# MAIN.net
KiCad netlist of a schematic drawn in Altium Designer
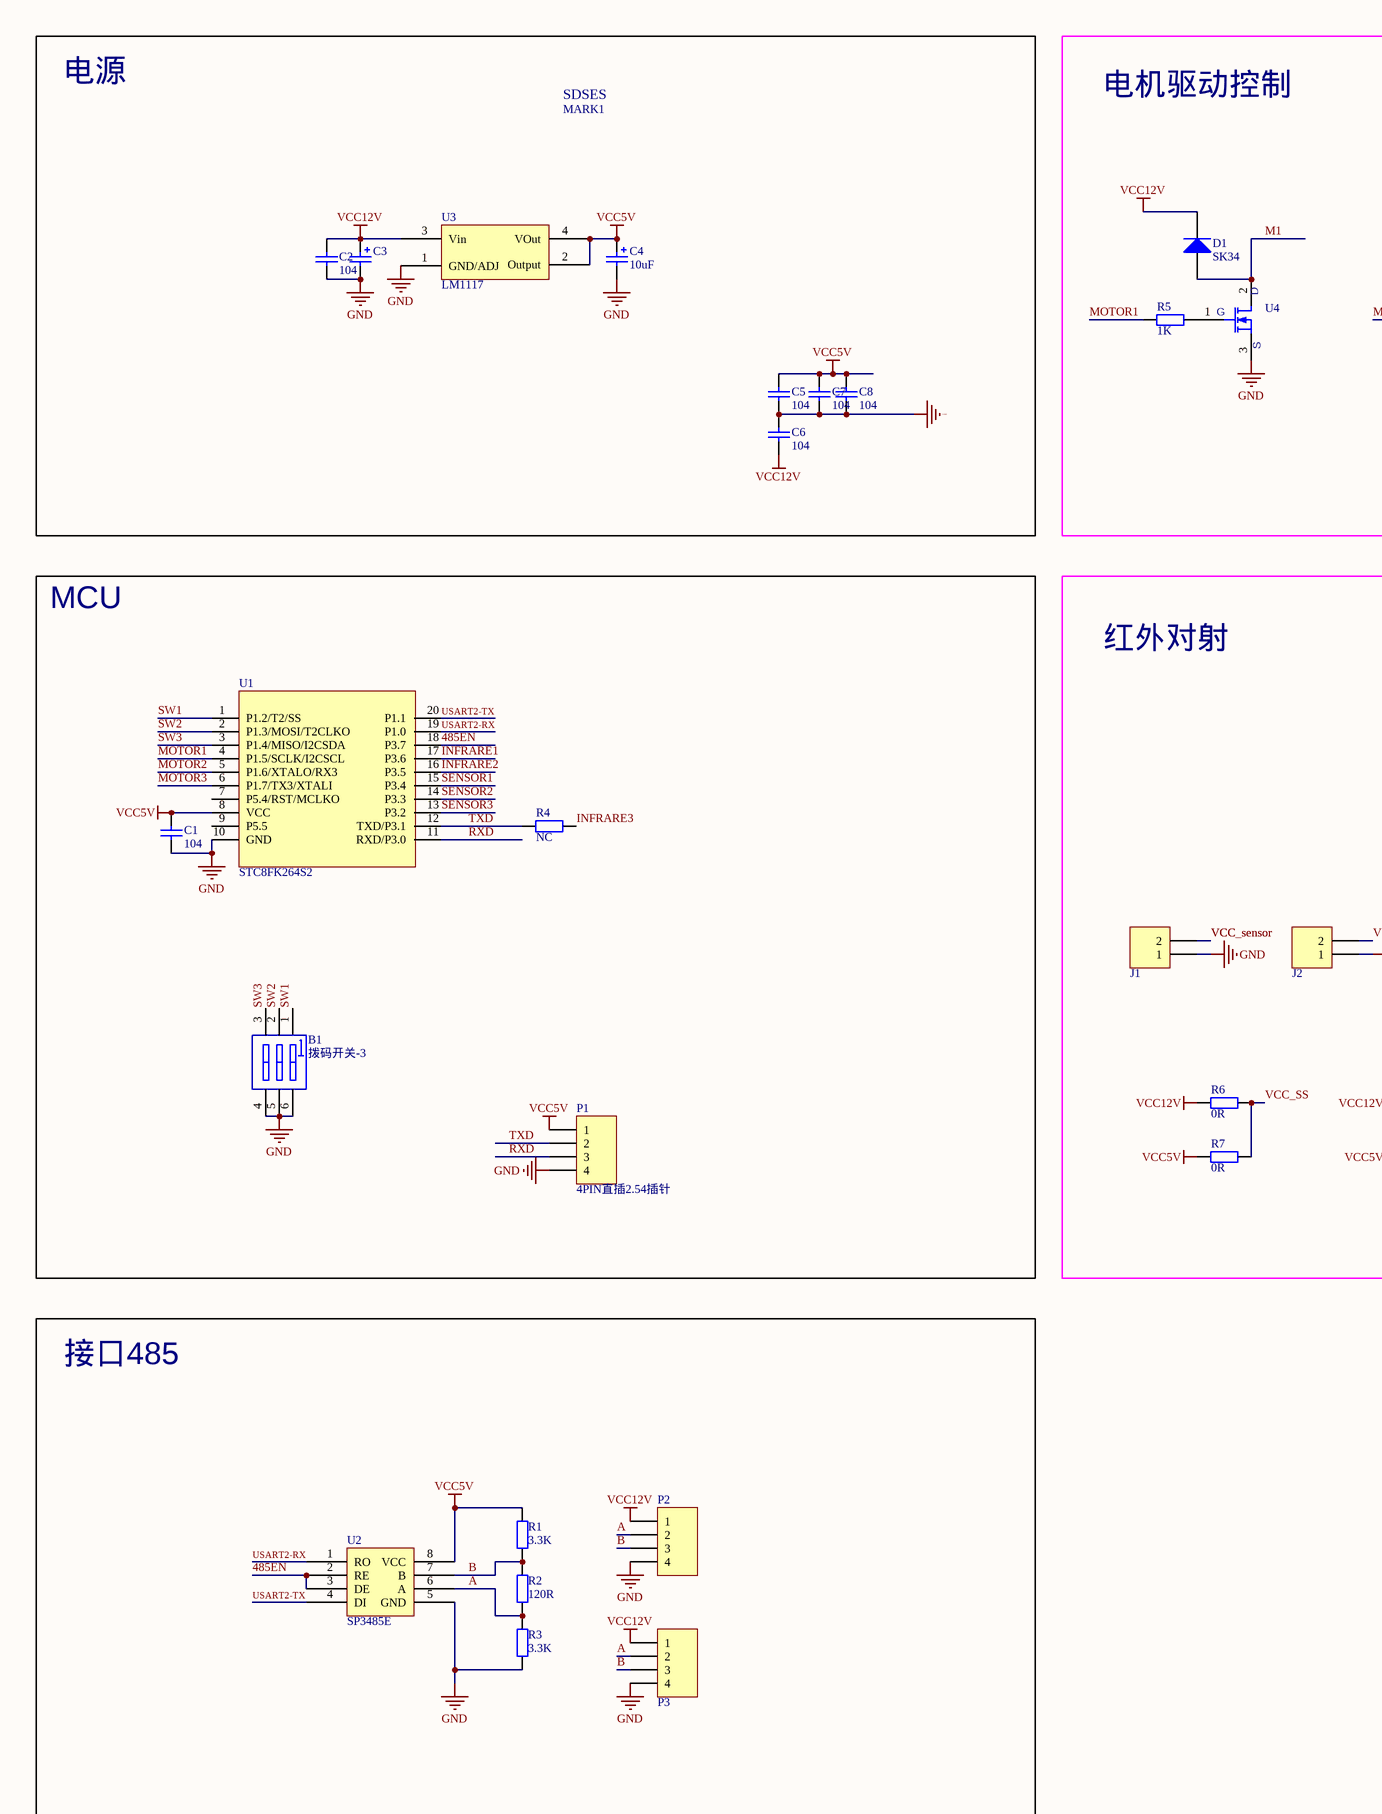
[diagram p0: MAIN.SchDoc, left]
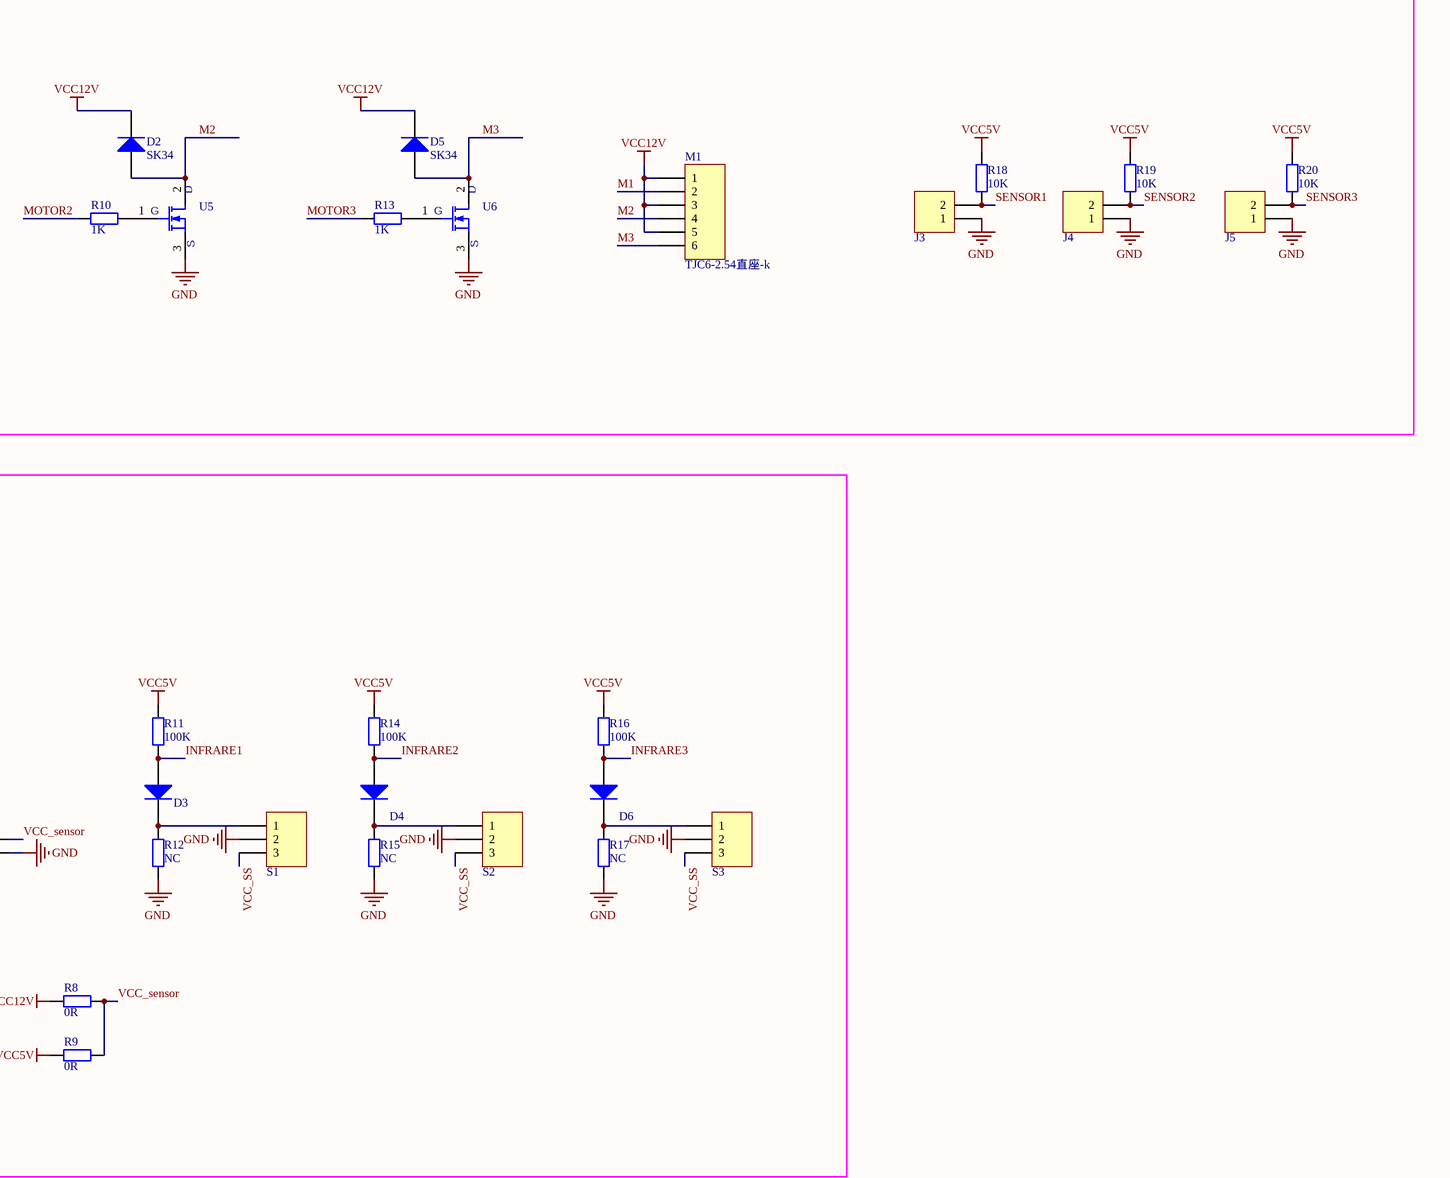
[diagram p1: MAIN.SchDoc, right]

(export (version "E")
  (design (tool "Eeschema 10.0.6"))
  (components
    (comp (ref "B1") (value "拨码开关-3") (footprint "DS-03-2.54") (libsource (lib "接插件") (part "拨码开关-3")))
    (comp (ref "C1")
      (value "Cap_0603")
      (footprint "0603C")
      (fields (field (name "型号") "104"))
      (libsource (lib "阻容晶体管元件") (part "Cap_0603"))
    )
    (comp (ref "C2")
      (value "Cap_0603")
      (footprint "0603C")
      (fields (field (name "型号") "104"))
      (libsource (lib "阻容晶体管元件") (part "Cap_0603"))
    )
    (comp (ref "C3")
      (value "Cap_直插470uf/16v")
      (footprint "cap_470/16v")
      (description "Polarized Capacitor (Radial)")
      (libsource (lib "阻容晶体管元件") (part "Cap_直插470uf/16v"))
    )
    (comp (ref "C4")
      (value "Cap_钽电容B-3528")
      (footprint "0805C")
      (description "Polarized Capacitor (Radial)")
      (fields (field (name "型号") "10uF"))
      (libsource (lib "阻容晶体管元件") (part "Cap_钽电容B-3528"))
    )
    (comp (ref "C5")
      (value "Cap_0603")
      (footprint "0603C")
      (fields (field (name "型号") "104"))
      (libsource (lib "阻容晶体管元件") (part "Cap_0603"))
    )
    (comp (ref "C6")
      (value "Cap_0603")
      (footprint "0603C")
      (fields (field (name "型号") "104"))
      (libsource (lib "阻容晶体管元件") (part "Cap_0603"))
    )
    (comp (ref "C7")
      (value "Cap_0603")
      (footprint "0603C")
      (fields (field (name "型号") "104"))
      (libsource (lib "阻容晶体管元件") (part "Cap_0603"))
    )
    (comp (ref "C8")
      (value "Cap_0603")
      (footprint "0603C")
      (fields (field (name "型号") "104"))
      (libsource (lib "阻容晶体管元件") (part "Cap_0603"))
    )
    (comp (ref "D1")
      (value "Diode_DO214AC")
      (footprint "DO_214AC_SMA")
      (description "Default Diode")
      (fields (field (name "型号") "SK34"))
      (libsource (lib "阻容晶体管元件") (part "Diode_DO214AC"))
    )
    (comp (ref "D2")
      (value "Diode_DO214AC")
      (footprint "DO_214AC_SMA")
      (description "Default Diode")
      (fields (field (name "型号") "SK34"))
      (libsource (lib "阻容晶体管元件") (part "Diode_DO214AC"))
    )
    (comp (ref "D3")
      (value "Diode_SOD323")
      (footprint "SOD323_D")
      (description "Default Diode")
      (fields (field (name "PUBLISHER") "Altium Limited"))
      (libsource (lib "阻容晶体管元件") (part "Diode_SOD323"))
    )
    (comp (ref "D4")
      (value "Diode_SOD323")
      (footprint "SOD323_D")
      (description "Default Diode")
      (fields (field (name "PUBLISHER") "Altium Limited"))
      (libsource (lib "阻容晶体管元件") (part "Diode_SOD323"))
    )
    (comp (ref "D5")
      (value "Diode_DO214AC")
      (footprint "DO_214AC_SMA")
      (description "Default Diode")
      (fields (field (name "型号") "SK34"))
      (libsource (lib "阻容晶体管元件") (part "Diode_DO214AC"))
    )
    (comp (ref "D6")
      (value "Diode_SOD323")
      (footprint "SOD323_D")
      (description "Default Diode")
      (fields (field (name "PUBLISHER") "Altium Limited"))
      (libsource (lib "阻容晶体管元件") (part "Diode_SOD323"))
    )
    (comp (ref "J1")
      (value "XHB2.54-2PIN-带锁扣")
      (footprint "SIP2")
      (description "Header, 4-Pin")
      (libsource (lib "接插件") (part "XHB2.54-2P直座"))
    )
    (comp (ref "J2")
      (value "XHB2.54-2PIN-带锁扣")
      (footprint "SIP2")
      (description "Header, 4-Pin")
      (libsource (lib "接插件") (part "XHB2.54-2P直座"))
    )
    (comp (ref "J3")
      (value "XHB2.54-2PIN-带锁扣")
      (footprint "SIP2")
      (description "Header, 4-Pin")
      (libsource (lib "接插件") (part "XHB2.54-2P直座"))
    )
    (comp (ref "J4")
      (value "XHB2.54-2PIN-带锁扣")
      (footprint "SIP2")
      (description "Header, 4-Pin")
      (libsource (lib "接插件") (part "XHB2.54-2P直座"))
    )
    (comp (ref "J5")
      (value "XHB2.54-2PIN-带锁扣")
      (footprint "SIP2")
      (description "Header, 4-Pin")
      (libsource (lib "接插件") (part "XHB2.54-2P直座"))
    )
    (comp (ref "M1")
      (value "TJC6-2.54直座-k")
      (footprint "SIP6")
      (description "Header, 6-Pin")
      (libsource (lib "接插件") (part "TJC6-2.54直座-k"))
    )
    (comp (ref "MARK1") (value "SDSES") (footprint "SDSES") (libsource (lib "集成电路") (part "SDSES")))
    (comp (ref "P1")
      (value "4PIN直插2.54插针")
      (footprint "SIP4_2D54F")
      (description "Header, 4-Pin")
      (libsource (lib "接插件") (part "4PIN直插2.54插针"))
    )
    (comp (ref "P2")
      (value "XHB2.54-4PIN直座")
      (footprint "SIP4")
      (description "Header, 4-Pin")
      (libsource (lib "接插件") (part "XHB2.54-4PIN直座"))
    )
    (comp (ref "P3")
      (value "XHB2.54-4PIN直座")
      (footprint "SIP4")
      (description "Header, 4-Pin")
      (libsource (lib "接插件") (part "XHB2.54-4PIN直座"))
    )
    (comp (ref "R1")
      (value "Res_0603")
      (footprint "0603R")
      (description "Resistor")
      (fields (field (name "型号") "3.3K"))
      (libsource (lib "") (part "Res_0603_1"))
    )
    (comp (ref "R2")
      (value "Res_0603")
      (footprint "0603R")
      (description "Resistor")
      (fields (field (name "型号") "120R"))
      (libsource (lib "") (part "Res_0603_1"))
    )
    (comp (ref "R3")
      (value "Res_0603")
      (footprint "0603R")
      (description "Resistor")
      (fields (field (name "型号") "3.3K"))
      (libsource (lib "") (part "Res_0603_1"))
    )
    (comp (ref "R4")
      (value "Res_0603")
      (footprint "0603R")
      (description "Resistor")
      (fields (field (name "型号") "NC"))
      (libsource (lib "") (part "Res_0603_3"))
    )
    (comp (ref "R5")
      (value "Res_0603")
      (footprint "0603R")
      (description "Resistor")
      (fields (field (name "型号") "1K"))
      (libsource (lib "阻容晶体管元件") (part "Res_0603"))
    )
    (comp (ref "R6")
      (value "Res_0603")
      (footprint "0603R")
      (description "Resistor")
      (fields (field (name "型号") "0R"))
      (libsource (lib "") (part "Res_0603_3"))
    )
    (comp (ref "R7")
      (value "Res_0603")
      (footprint "0603R")
      (description "Resistor")
      (fields (field (name "型号") "0R"))
      (libsource (lib "") (part "Res_0603_3"))
    )
    (comp (ref "R8")
      (value "Res_0603")
      (footprint "0603R")
      (description "Resistor")
      (fields (field (name "型号") "0R"))
      (libsource (lib "") (part "Res_0603_3"))
    )
    (comp (ref "R9")
      (value "Res_0603")
      (footprint "0603R")
      (description "Resistor")
      (fields (field (name "型号") "0R"))
      (libsource (lib "") (part "Res_0603_3"))
    )
    (comp (ref "R10")
      (value "Res_0603")
      (footprint "0603R")
      (description "Resistor")
      (fields (field (name "型号") "1K"))
      (libsource (lib "阻容晶体管元件") (part "Res_0603"))
    )
    (comp (ref "R11")
      (value "Res_0603")
      (footprint "0603R")
      (description "Resistor")
      (fields (field (name "型号") "100K"))
      (libsource (lib "") (part "Res_0603_1"))
    )
    (comp (ref "R12")
      (value "Res_0603")
      (footprint "0603R")
      (description "Resistor")
      (fields (field (name "型号") "NC"))
      (libsource (lib "") (part "Res_0603_1"))
    )
    (comp (ref "R13")
      (value "Res_0603")
      (footprint "0603R")
      (description "Resistor")
      (fields (field (name "型号") "1K"))
      (libsource (lib "阻容晶体管元件") (part "Res_0603"))
    )
    (comp (ref "R14")
      (value "Res_0603")
      (footprint "0603R")
      (description "Resistor")
      (fields (field (name "型号") "100K"))
      (libsource (lib "") (part "Res_0603_1"))
    )
    (comp (ref "R15")
      (value "Res_0603")
      (footprint "0603R")
      (description "Resistor")
      (fields (field (name "型号") "NC"))
      (libsource (lib "") (part "Res_0603_1"))
    )
    (comp (ref "R16")
      (value "Res_0603")
      (footprint "0603R")
      (description "Resistor")
      (fields (field (name "型号") "100K"))
      (libsource (lib "") (part "Res_0603_1"))
    )
    (comp (ref "R17")
      (value "Res_0603")
      (footprint "0603R")
      (description "Resistor")
      (fields (field (name "型号") "NC"))
      (libsource (lib "") (part "Res_0603_1"))
    )
    (comp (ref "R18")
      (value "Res_0603")
      (footprint "0603R")
      (description "Resistor")
      (fields (field (name "型号") "10K"))
      (libsource (lib "") (part "Res_0603_2"))
    )
    (comp (ref "R19")
      (value "Res_0603")
      (footprint "0603R")
      (description "Resistor")
      (fields (field (name "型号") "10K"))
      (libsource (lib "") (part "Res_0603_2"))
    )
    (comp (ref "R20")
      (value "Res_0603")
      (footprint "0603R")
      (description "Resistor")
      (fields (field (name "型号") "10K"))
      (libsource (lib "") (part "Res_0603_2"))
    )
    (comp (ref "S1")
      (value "TJC3-2.54直座")
      (footprint "SIP3")
      (description "Header, 3-Pin")
      (libsource (lib "接插件") (part "TJC3-2.54直座"))
    )
    (comp (ref "S2")
      (value "TJC3-2.54直座")
      (footprint "SIP3")
      (description "Header, 3-Pin")
      (libsource (lib "接插件") (part "TJC3-2.54直座"))
    )
    (comp (ref "S3")
      (value "TJC3-2.54直座")
      (footprint "SIP3")
      (description "Header, 3-Pin")
      (libsource (lib "接插件") (part "TJC3-2.54直座"))
    )
    (comp (ref "U1")
      (value "STC8FK264S2")
      (footprint "SSOP20")
      (fields (field (name "型号") "STC8FK264S2"))
      (libsource (lib "集成电路") (part "STC8FK264S2"))
    )
    (comp (ref "U2") (value "SP3485E") (footprint "SO_8") (libsource (lib "集成电路") (part "SP485E")))
    (comp (ref "U3") (value "LM1117") (footprint "SOT223") (libsource (lib "集成电路") (part "LM1117")))
    (comp (ref "U4") (value "NMOS") (footprint "TO-252-2") (libsource (lib "集成电路") (part "NMOS")))
    (comp (ref "U5") (value "NMOS") (footprint "TO-252-2") (libsource (lib "集成电路") (part "NMOS")))
    (comp (ref "U6") (value "NMOS") (footprint "TO-252-2") (libsource (lib "集成电路") (part "NMOS")))
  )
  (nets
    (net (code "1") (name "/485EN") (class "Default")
      (node (ref "U1") (pin "18") (pinfunction "P3.7_18") (pintype "passive"))
      (node (ref "U2") (pin "2") (pinfunction "RE_2") (pintype "passive"))
      (node (ref "U2") (pin "3") (pinfunction "DE_3") (pintype "passive"))
    )
    (net (code "2") (name "/A") (class "Default")
      (node (ref "P2") (pin "2") (pinfunction "2_2") (pintype "passive"))
      (node (ref "P3") (pin "2") (pinfunction "2_2") (pintype "passive"))
      (node (ref "R2") (pin "1") (pinfunction "1_1") (pintype "passive"))
      (node (ref "R3") (pin "2") (pinfunction "2_2") (pintype "passive"))
      (node (ref "U2") (pin "6") (pinfunction "A_6") (pintype "passive"))
    )
    (net (code "3") (name "/B") (class "Default")
      (node (ref "P2") (pin "3") (pinfunction "3_3") (pintype "passive"))
      (node (ref "P3") (pin "3") (pinfunction "3_3") (pintype "passive"))
      (node (ref "R1") (pin "1") (pinfunction "1_1") (pintype "passive"))
      (node (ref "R2") (pin "2") (pinfunction "2_2") (pintype "passive"))
      (node (ref "U2") (pin "7") (pinfunction "B_7") (pintype "passive"))
    )
    (net (code "4") (name "/INFRARE1") (class "Default")
      (node (ref "D3") (pin "1") (pinfunction "1_1") (pintype "passive"))
      (node (ref "R11") (pin "1") (pinfunction "1_1") (pintype "passive"))
      (node (ref "U1") (pin "17") (pinfunction "P3.6_17") (pintype "passive"))
    )
    (net (code "5") (name "/INFRARE2") (class "Default")
      (node (ref "D4") (pin "1") (pinfunction "1_1") (pintype "passive"))
      (node (ref "R14") (pin "1") (pinfunction "1_1") (pintype "passive"))
      (node (ref "U1") (pin "16") (pinfunction "P3.5_16") (pintype "passive"))
    )
    (net (code "6") (name "/INFRARE3") (class "Default")
      (node (ref "D6") (pin "1") (pinfunction "1_1") (pintype "passive"))
      (node (ref "R16") (pin "1") (pinfunction "1_1") (pintype "passive"))
      (node (ref "R4") (pin "1") (pinfunction "1_1") (pintype "passive"))
    )
    (net (code "7") (name "/M1") (class "Default")
      (node (ref "D1") (pin "1") (pinfunction "1_1") (pintype "passive"))
      (node (ref "M1") (pin "2") (pinfunction "2_2") (pintype "passive"))
      (node (ref "U4") (pin "2") (pinfunction "D_2") (pintype "passive"))
    )
    (net (code "8") (name "/M2") (class "Default")
      (node (ref "D2") (pin "1") (pinfunction "1_1") (pintype "passive"))
      (node (ref "M1") (pin "4") (pinfunction "4_4") (pintype "passive"))
      (node (ref "U5") (pin "2") (pinfunction "D_2") (pintype "passive"))
    )
    (net (code "9") (name "/M3") (class "Default")
      (node (ref "D5") (pin "1") (pinfunction "1_1") (pintype "passive"))
      (node (ref "M1") (pin "6") (pinfunction "6_6") (pintype "passive"))
      (node (ref "U6") (pin "2") (pinfunction "D_2") (pintype "passive"))
    )
    (net (code "10") (name "/MOTOR1") (class "Default")
      (node (ref "R5") (pin "1") (pinfunction "1_1") (pintype "passive"))
      (node (ref "U1") (pin "4") (pinfunction "P1.5/SCLK/I2CSCL_4") (pintype "passive"))
    )
    (net (code "11") (name "/MOTOR2") (class "Default")
      (node (ref "R10") (pin "1") (pinfunction "1_1") (pintype "passive"))
      (node (ref "U1") (pin "5") (pinfunction "P1.6/XTALO/RX3_5") (pintype "passive"))
    )
    (net (code "12") (name "/MOTOR3") (class "Default")
      (node (ref "R13") (pin "1") (pinfunction "1_1") (pintype "passive"))
      (node (ref "U1") (pin "6") (pinfunction "P1.7/TX3/XTALI_6") (pintype "passive"))
    )
    (net (code "13") (name "/RXD") (class "Default")
      (node (ref "P1") (pin "3") (pinfunction "3_3") (pintype "passive"))
      (node (ref "U1") (pin "11") (pinfunction "RXD/P3.0_11") (pintype "passive"))
    )
    (net (code "14") (name "/SENSOR1") (class "Default")
      (node (ref "J3") (pin "2") (pinfunction "2_2") (pintype "passive"))
      (node (ref "R18") (pin "2") (pinfunction "2_2") (pintype "passive"))
      (node (ref "U1") (pin "15") (pinfunction "P3.4_15") (pintype "passive"))
    )
    (net (code "15") (name "/SENSOR2") (class "Default")
      (node (ref "J4") (pin "2") (pinfunction "2_2") (pintype "passive"))
      (node (ref "R19") (pin "2") (pinfunction "2_2") (pintype "passive"))
      (node (ref "U1") (pin "14") (pinfunction "P3.3_14") (pintype "passive"))
    )
    (net (code "16") (name "/SENSOR3") (class "Default")
      (node (ref "J5") (pin "2") (pinfunction "2_2") (pintype "passive"))
      (node (ref "R20") (pin "2") (pinfunction "2_2") (pintype "passive"))
      (node (ref "U1") (pin "13") (pinfunction "P3.2_13") (pintype "passive"))
    )
    (net (code "17") (name "/SW1") (class "Default")
      (node (ref "B1") (pin "1") (pinfunction "A1_1") (pintype "passive"))
      (node (ref "U1") (pin "1") (pinfunction "P1.2/T2/SS_1") (pintype "passive"))
    )
    (net (code "18") (name "/SW2") (class "Default")
      (node (ref "B1") (pin "2") (pinfunction "2_2") (pintype "passive"))
      (node (ref "U1") (pin "2") (pinfunction "P1.3/MOSI/T2CLKO_2") (pintype "passive"))
    )
    (net (code "19") (name "/SW3") (class "Default")
      (node (ref "B1") (pin "3") (pinfunction "3_3") (pintype "passive"))
      (node (ref "U1") (pin "3") (pinfunction "P1.4/MISO/I2CSDA_3") (pintype "passive"))
    )
    (net (code "20") (name "/TXD") (class "Default")
      (node (ref "P1") (pin "2") (pinfunction "2_2") (pintype "passive"))
      (node (ref "R4") (pin "2") (pinfunction "2_2") (pintype "passive"))
      (node (ref "U1") (pin "12") (pinfunction "TXD/P3.1_12") (pintype "passive"))
    )
    (net (code "21") (name "/USART2-RX") (class "Default")
      (node (ref "U1") (pin "19") (pinfunction "P1.0_19") (pintype "passive"))
      (node (ref "U2") (pin "1") (pinfunction "RO_1") (pintype "passive"))
    )
    (net (code "22") (name "/USART2-TX") (class "Default")
      (node (ref "U1") (pin "20") (pinfunction "P1.1_20") (pintype "passive"))
      (node (ref "U2") (pin "4") (pinfunction "DI_4") (pintype "passive"))
    )
    (net (code "23") (name "/VCC_SS") (class "Default")
      (node (ref "R6") (pin "1") (pinfunction "1_1") (pintype "passive"))
      (node (ref "R7") (pin "1") (pinfunction "1_1") (pintype "passive"))
      (node (ref "S1") (pin "3") (pinfunction "3_3") (pintype "passive"))
      (node (ref "S2") (pin "3") (pinfunction "3_3") (pintype "passive"))
      (node (ref "S3") (pin "3") (pinfunction "3_3") (pintype "passive"))
    )
    (net (code "24") (name "/VCC_sensor") (class "Default")
      (node (ref "J1") (pin "2") (pinfunction "2_2") (pintype "passive"))
      (node (ref "J2") (pin "2") (pinfunction "2_2") (pintype "passive"))
      (node (ref "R8") (pin "1") (pinfunction "1_1") (pintype "passive"))
      (node (ref "R9") (pin "1") (pinfunction "1_1") (pintype "passive"))
    )
    (net (code "25") (name "GND") (class "Default")
      (node (ref "B1") (pin "4") (pinfunction "4_4") (pintype "passive"))
      (node (ref "B1") (pin "5") (pinfunction "5_5") (pintype "passive"))
      (node (ref "B1") (pin "6") (pinfunction "6_6") (pintype "passive"))
      (node (ref "C1") (pin "1") (pinfunction "1_1") (pintype "passive"))
      (node (ref "C2") (pin "1") (pinfunction "1_1") (pintype "passive"))
      (node (ref "C3") (pin "2") (pinfunction "2_2") (pintype "passive"))
      (node (ref "C4") (pin "2") (pinfunction "2_2") (pintype "passive"))
      (node (ref "C5") (pin "2") (pinfunction "2_2") (pintype "passive"))
      (node (ref "C6") (pin "2") (pinfunction "2_2") (pintype "passive"))
      (node (ref "C7") (pin "1") (pinfunction "1_1") (pintype "passive"))
      (node (ref "C8") (pin "1") (pinfunction "1_1") (pintype "passive"))
      (node (ref "J1") (pin "1") (pinfunction "1_1") (pintype "passive"))
      (node (ref "J2") (pin "1") (pinfunction "1_1") (pintype "passive"))
      (node (ref "J3") (pin "1") (pinfunction "1_1") (pintype "passive"))
      (node (ref "J4") (pin "1") (pinfunction "1_1") (pintype "passive"))
      (node (ref "J5") (pin "1") (pinfunction "1_1") (pintype "passive"))
      (node (ref "P1") (pin "4") (pinfunction "4_4") (pintype "passive"))
      (node (ref "P2") (pin "4") (pinfunction "4_4") (pintype "passive"))
      (node (ref "P3") (pin "4") (pinfunction "4_4") (pintype "passive"))
      (node (ref "R12") (pin "1") (pinfunction "1_1") (pintype "passive"))
      (node (ref "R15") (pin "1") (pinfunction "1_1") (pintype "passive"))
      (node (ref "R17") (pin "1") (pinfunction "1_1") (pintype "passive"))
      (node (ref "R3") (pin "1") (pinfunction "1_1") (pintype "passive"))
      (node (ref "S1") (pin "2") (pinfunction "2_2") (pintype "passive"))
      (node (ref "S2") (pin "2") (pinfunction "2_2") (pintype "passive"))
      (node (ref "S3") (pin "2") (pinfunction "2_2") (pintype "passive"))
      (node (ref "U1") (pin "10") (pinfunction "GND_10") (pintype "passive"))
      (node (ref "U2") (pin "5") (pinfunction "GND_5") (pintype "passive"))
      (node (ref "U3") (pin "1") (pinfunction "GND/ADJ_1") (pintype "passive"))
      (node (ref "U4") (pin "3") (pinfunction "S_3") (pintype "passive"))
      (node (ref "U5") (pin "3") (pinfunction "S_3") (pintype "passive"))
      (node (ref "U6") (pin "3") (pinfunction "S_3") (pintype "passive"))
    )
    (net (code "26") (name "Net-(D3-Pad2)") (class "Default")
      (node (ref "D3") (pin "2") (pinfunction "2_2") (pintype "passive"))
      (node (ref "R12") (pin "2") (pinfunction "2_2") (pintype "passive"))
      (node (ref "S1") (pin "1") (pinfunction "1_1") (pintype "passive"))
    )
    (net (code "27") (name "Net-(D4-Pad2)") (class "Default")
      (node (ref "D4") (pin "2") (pinfunction "2_2") (pintype "passive"))
      (node (ref "R15") (pin "2") (pinfunction "2_2") (pintype "passive"))
      (node (ref "S2") (pin "1") (pinfunction "1_1") (pintype "passive"))
    )
    (net (code "28") (name "Net-(D6-Pad2)") (class "Default")
      (node (ref "D6") (pin "2") (pinfunction "2_2") (pintype "passive"))
      (node (ref "R17") (pin "2") (pinfunction "2_2") (pintype "passive"))
      (node (ref "S3") (pin "1") (pinfunction "1_1") (pintype "passive"))
    )
    (net (code "29") (name "Net-(U4-G)") (class "Default")
      (node (ref "R5") (pin "2") (pinfunction "2_2") (pintype "passive"))
      (node (ref "U4") (pin "1") (pinfunction "G_1") (pintype "passive"))
    )
    (net (code "30") (name "Net-(U5-G)") (class "Default")
      (node (ref "R10") (pin "2") (pinfunction "2_2") (pintype "passive"))
      (node (ref "U5") (pin "1") (pinfunction "G_1") (pintype "passive"))
    )
    (net (code "31") (name "Net-(U6-G)") (class "Default")
      (node (ref "R13") (pin "2") (pinfunction "2_2") (pintype "passive"))
      (node (ref "U6") (pin "1") (pinfunction "G_1") (pintype "passive"))
    )
    (net (code "32") (name "VCC5V") (class "Default")
      (node (ref "C1") (pin "2") (pinfunction "2_2") (pintype "passive"))
      (node (ref "C4") (pin "1") (pinfunction "1_1") (pintype "passive"))
      (node (ref "C5") (pin "1") (pinfunction "1_1") (pintype "passive"))
      (node (ref "C7") (pin "2") (pinfunction "2_2") (pintype "passive"))
      (node (ref "C8") (pin "2") (pinfunction "2_2") (pintype "passive"))
      (node (ref "P1") (pin "1") (pinfunction "1_1") (pintype "passive"))
      (node (ref "R1") (pin "2") (pinfunction "2_2") (pintype "passive"))
      (node (ref "R11") (pin "2") (pinfunction "2_2") (pintype "passive"))
      (node (ref "R14") (pin "2") (pinfunction "2_2") (pintype "passive"))
      (node (ref "R16") (pin "2") (pinfunction "2_2") (pintype "passive"))
      (node (ref "R18") (pin "1") (pinfunction "1_1") (pintype "passive"))
      (node (ref "R19") (pin "1") (pinfunction "1_1") (pintype "passive"))
      (node (ref "R20") (pin "1") (pinfunction "1_1") (pintype "passive"))
      (node (ref "R7") (pin "2") (pinfunction "2_2") (pintype "passive"))
      (node (ref "R9") (pin "2") (pinfunction "2_2") (pintype "passive"))
      (node (ref "U1") (pin "8") (pinfunction "VCC_8") (pintype "passive"))
      (node (ref "U2") (pin "8") (pinfunction "VCC_8") (pintype "passive"))
      (node (ref "U3") (pin "2") (pinfunction "Output_2") (pintype "passive"))
      (node (ref "U3") (pin "4") (pinfunction "VOut_4") (pintype "passive"))
    )
    (net (code "33") (name "VCC12V") (class "Default")
      (node (ref "C2") (pin "2") (pinfunction "2_2") (pintype "passive"))
      (node (ref "C3") (pin "1") (pinfunction "1_1") (pintype "passive"))
      (node (ref "C6") (pin "1") (pinfunction "1_1") (pintype "passive"))
      (node (ref "D1") (pin "2") (pinfunction "2_2") (pintype "passive"))
      (node (ref "D2") (pin "2") (pinfunction "2_2") (pintype "passive"))
      (node (ref "D5") (pin "2") (pinfunction "2_2") (pintype "passive"))
      (node (ref "M1") (pin "1") (pinfunction "1_1") (pintype "passive"))
      (node (ref "M1") (pin "3") (pinfunction "3_3") (pintype "passive"))
      (node (ref "M1") (pin "5") (pinfunction "5_5") (pintype "passive"))
      (node (ref "P2") (pin "1") (pinfunction "1_1") (pintype "passive"))
      (node (ref "P3") (pin "1") (pinfunction "1_1") (pintype "passive"))
      (node (ref "R6") (pin "2") (pinfunction "2_2") (pintype "passive"))
      (node (ref "R8") (pin "2") (pinfunction "2_2") (pintype "passive"))
      (node (ref "U3") (pin "3") (pinfunction "Vin_3") (pintype "passive"))
    )
    (net (code "34") (name "unconnected-(U1-P5.4{slash}RST{slash}MCLKO-Pad7)") (class "Default")
      (node (ref "U1") (pin "7") (pinfunction "P5.4/RST/MCLKO_7") (pintype "passive"))
    )
    (net (code "35") (name "unconnected-(U1-P5.5-Pad9)") (class "Default")
      (node (ref "U1") (pin "9") (pinfunction "P5.5_9") (pintype "passive"))
    )
  )
)
